# Sequencer-V01-010-eagle7.net
KiCad netlist of a schematic drawn in EAGLE
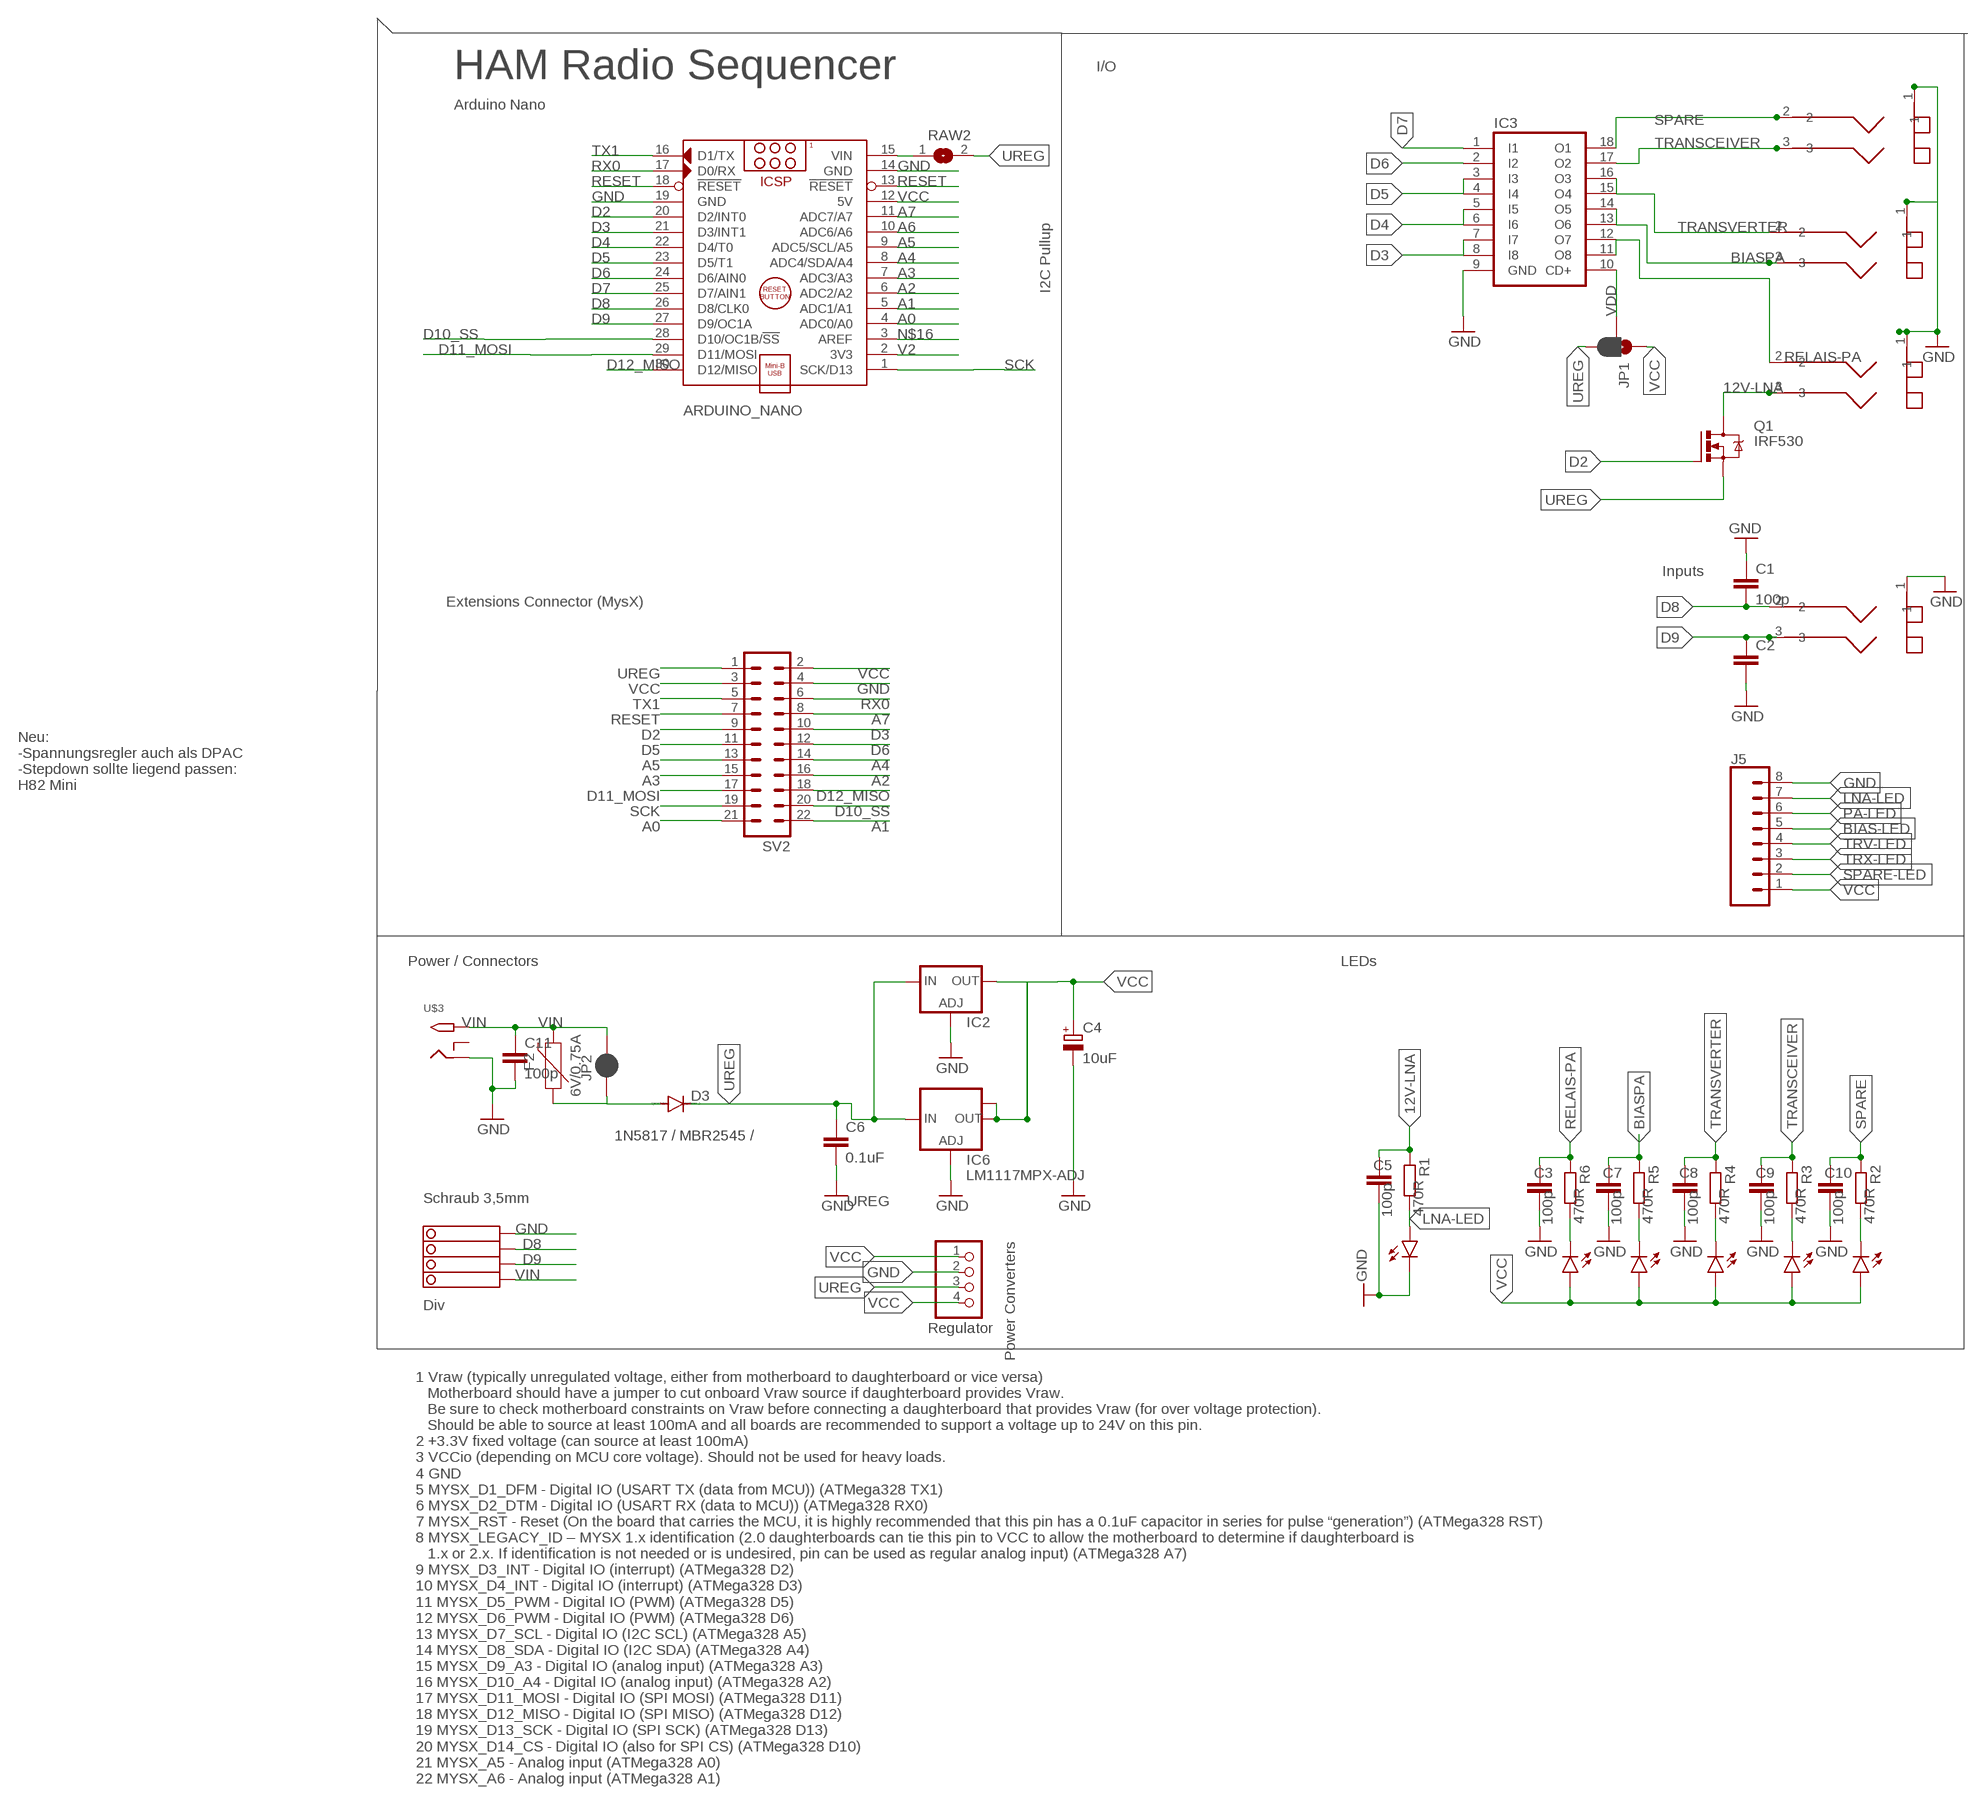
[diagram p0: schematic, sheet 1]

(export (version "E")
  (design (tool "Eeschema 10.0.6"))
  (components
    (comp (ref "ARDUINO_NANO")
      (value "ARDUINO_NANO_OHNE-BOHR")
      (footprint "eagle-import:ARDUINO_NANO")
      (libsource (lib "eagle-import") (part "ARDUINO_NANO_OHNE-BOHR"))
    )
    (comp (ref "C1")
      (value "100p")
      (footprint "eagle-import:C025-025X050")
      (libsource (lib "eagle-import") (part "C-EU025-025X050"))
    )
    (comp (ref "C2")
      (value "C-EU025-025X050")
      (footprint "eagle-import:C025-025X050")
      (libsource (lib "eagle-import") (part "C-EU025-025X050"))
    )
    (comp (ref "C3")
      (value "100p")
      (footprint "eagle-import:C025-025X050")
      (libsource (lib "eagle-import") (part "C-EU025-025X050"))
    )
    (comp (ref "C4")
      (value "10uF")
      (footprint "eagle-import:E3,5-8")
      (libsource (lib "eagle-import") (part "CPOL-EUE3.5-8"))
    )
    (comp (ref "C5")
      (value "100p")
      (footprint "eagle-import:C025-025X050")
      (libsource (lib "eagle-import") (part "C-EU025-025X050"))
    )
    (comp (ref "C6")
      (value "0.1uF")
      (footprint "eagle-import:C050-024X044")
      (libsource (lib "eagle-import") (part "C-EU050-024X044"))
    )
    (comp (ref "C7")
      (value "100p")
      (footprint "eagle-import:C025-025X050")
      (libsource (lib "eagle-import") (part "C-EU025-025X050"))
    )
    (comp (ref "C8")
      (value "100p")
      (footprint "eagle-import:C025-025X050")
      (libsource (lib "eagle-import") (part "C-EU025-025X050"))
    )
    (comp (ref "C9")
      (value "100p")
      (footprint "eagle-import:C025-025X050")
      (libsource (lib "eagle-import") (part "C-EU025-025X050"))
    )
    (comp (ref "C10")
      (value "100p")
      (footprint "eagle-import:C025-025X050")
      (libsource (lib "eagle-import") (part "C-EU025-025X050"))
    )
    (comp (ref "C11")
      (value "100p")
      (footprint "eagle-import:C025-025X050")
      (libsource (lib "eagle-import") (part "C-EU025-025X050"))
    )
    (comp (ref "D3")
      (value "1N5817 / MBR2545 /")
      (footprint "eagle-import:D-2.5")
      (libsource (lib "eagle-import") (part "DIODE-D-2.5"))
    )
    (comp (ref "F2")
      (value "6V/0.75A")
      (footprint "eagle-import:1206")
      (libsource (lib "eagle-import") (part "PPTC_THREE-QUARTER-AMP"))
    )
    (comp (ref "IC2")
      (value "LD117ADT50TR")
      (footprint "eagle-import:DPACK")
      (libsource (lib "eagle-import") (part "LD117A?DT50TR"))
    )
    (comp (ref "IC3")
      (value "ULN2803A")
      (footprint "eagle-import:DIL18")
      (libsource (lib "eagle-import") (part "ULN2803A"))
    )
    (comp (ref "IC6")
      (value "LM1117MPX-ADJ")
      (footprint "eagle-import:SOT223")
      (libsource (lib "eagle-import") (part "LM1117MPX-ADJ"))
    )
    (comp (ref "J1")
      (value "RCJ-2234")
      (footprint "eagle-import:RCJ-2221")
      (fields (field (name "MF") "CUI Devices"))
      (libsource (lib "eagle-import") (part "RCJ-2234"))
    )
    (comp (ref "J2")
      (value "RCJ-2234")
      (footprint "eagle-import:RCJ-2221")
      (fields (field (name "MF") "CUI Devices"))
      (libsource (lib "eagle-import") (part "RCJ-2234"))
    )
    (comp (ref "J3")
      (value "RCJ-2234")
      (footprint "eagle-import:RCJ-2221")
      (fields (field (name "MF") "CUI Devices"))
      (libsource (lib "eagle-import") (part "RCJ-2234"))
    )
    (comp (ref "J4")
      (value "RCJ-2234")
      (footprint "eagle-import:RCJ-2221")
      (fields (field (name "MF") "CUI Devices"))
      (libsource (lib "eagle-import") (part "RCJ-2234"))
    )
    (comp (ref "J5")
      (value "CONN_08LOCK")
      (footprint "eagle-import:1X08_LOCK")
      (libsource (lib "eagle-import") (part "CONN_08LOCK"))
    )
    (comp (ref "JP1")
      (value "JUMPER-SMT_3_1-NC_PASTE_NO-SILK")
      (footprint "eagle-import:SMT-JUMPER_3_1-NC_PASTE_NO-SILK")
      (libsource (lib "eagle-import") (part "JUMPER-SMT_3_1-NC_PASTE_NO-SILK"))
    )
    (comp (ref "JP2")
      (value "JUMPER-SMT_2_NC_PASTE_NO-SILK")
      (footprint "eagle-import:SMT-JUMPER_2_NC_PASTE_NO-SILK")
      (libsource (lib "eagle-import") (part "JUMPER-SMT_2_NC_PASTE_NO-SILK"))
    )
    (comp (ref "LED1")
      (value "LED3MM")
      (footprint "eagle-import:LED3MM")
      (libsource (lib "eagle-import") (part "LED3MM"))
    )
    (comp (ref "LED2")
      (value "LED3MM")
      (footprint "eagle-import:LED3MM")
      (libsource (lib "eagle-import") (part "LED3MM"))
    )
    (comp (ref "LED3")
      (value "LED3MM")
      (footprint "eagle-import:LED3MM")
      (libsource (lib "eagle-import") (part "LED3MM"))
    )
    (comp (ref "LED4")
      (value "LED3MM")
      (footprint "eagle-import:LED3MM")
      (libsource (lib "eagle-import") (part "LED3MM"))
    )
    (comp (ref "LED5")
      (value "LED3MM")
      (footprint "eagle-import:LED3MM")
      (libsource (lib "eagle-import") (part "LED3MM"))
    )
    (comp (ref "LED6")
      (value "LED3MM")
      (footprint "eagle-import:LED3MM")
      (libsource (lib "eagle-import") (part "LED3MM"))
    )
    (comp (ref "Q1")
      (value "IRF530")
      (footprint "eagle-import:TO220BV")
      (libsource (lib "eagle-import") (part "IRF530"))
    )
    (comp (ref "R1")
      (value "470R")
      (footprint "eagle-import:0204_5")
      (libsource (lib "eagle-import") (part "R-EU_0204/5"))
    )
    (comp (ref "R2")
      (value "470R")
      (footprint "eagle-import:0204_5")
      (libsource (lib "eagle-import") (part "R-EU_0204/5"))
    )
    (comp (ref "R3")
      (value "470R")
      (footprint "eagle-import:0204_5")
      (libsource (lib "eagle-import") (part "R-EU_0204/5"))
    )
    (comp (ref "R4")
      (value "470R")
      (footprint "eagle-import:0204_5")
      (libsource (lib "eagle-import") (part "R-EU_0204/5"))
    )
    (comp (ref "R5")
      (value "470R")
      (footprint "eagle-import:0204_5")
      (libsource (lib "eagle-import") (part "R-EU_0204/5"))
    )
    (comp (ref "R6")
      (value "470R")
      (footprint "eagle-import:0204_5")
      (libsource (lib "eagle-import") (part "R-EU_0204/5"))
    )
    (comp (ref "RAW2")
      (value "SJ")
      (footprint "eagle-import:SJ")
      (libsource (lib "eagle-import") (part "SJ"))
    )
    (comp (ref "STEPDWN")
      (value "PINHD-1X04_2.54-S")
      (footprint "eagle-import:1X04-S")
      (libsource (lib "eagle-import") (part "PINHD-1X04_2.54-S"))
    )
    (comp (ref "SV2")
      (value "MA11-2")
      (footprint "eagle-import:MA11-2")
      (libsource (lib "eagle-import") (part "MA11-2"))
    )
    (comp (ref "U$3")
      (value "2.1MMJACKTHM")
      (footprint "eagle-import:PJ-102A")
      (libsource (lib "eagle-import") (part "2.1MMJACKTHM"))
    )
    (comp (ref "X4")
      (value "1751264")
      (footprint "eagle-import:1751264")
      (libsource (lib "eagle-import") (part "1751264"))
    )
  )
  (nets
    (net (code "1") (name "/A0") (class "Default")
      (node (ref "ARDUINO_NANO") (pin "4") (pinfunction "ADC0/A0_4") (pintype "bidirectional"))
      (node (ref "SV2") (pin "21") (pinfunction "21_21") (pintype "passive"))
    )
    (net (code "2") (name "/A1") (class "Default")
      (node (ref "ARDUINO_NANO") (pin "5") (pinfunction "ADC1/A1_5") (pintype "bidirectional"))
      (node (ref "SV2") (pin "22") (pinfunction "22_22") (pintype "passive"))
    )
    (net (code "3") (name "/A2") (class "Default")
      (node (ref "ARDUINO_NANO") (pin "6") (pinfunction "ADC2/A2_6") (pintype "bidirectional"))
      (node (ref "SV2") (pin "16") (pinfunction "16_16") (pintype "passive"))
    )
    (net (code "4") (name "/A3") (class "Default")
      (node (ref "ARDUINO_NANO") (pin "7") (pinfunction "ADC3/A3_7") (pintype "bidirectional"))
      (node (ref "SV2") (pin "15") (pinfunction "15_15") (pintype "passive"))
    )
    (net (code "5") (name "/A4") (class "Default")
      (node (ref "ARDUINO_NANO") (pin "8") (pinfunction "ADC4/SDA/A4_8") (pintype "bidirectional"))
      (node (ref "SV2") (pin "14") (pinfunction "14_14") (pintype "passive"))
    )
    (net (code "6") (name "/A5") (class "Default")
      (node (ref "ARDUINO_NANO") (pin "9") (pinfunction "ADC5/SCL/A5_9") (pintype "bidirectional"))
      (node (ref "SV2") (pin "13") (pinfunction "13_13") (pintype "passive"))
    )
    (net (code "7") (name "/A6") (class "Default")
      (node (ref "ARDUINO_NANO") (pin "10") (pinfunction "ADC6/A6_10") (pintype "bidirectional"))
    )
    (net (code "8") (name "/A7") (class "Default")
      (node (ref "ARDUINO_NANO") (pin "11") (pinfunction "ADC7/A7_11") (pintype "bidirectional"))
      (node (ref "SV2") (pin "8") (pinfunction "8_8") (pintype "passive"))
    )
    (net (code "9") (name "/D10_SS") (class "Default")
      (node (ref "ARDUINO_NANO") (pin "28") (pinfunction "D10/OC1B/~{SS}_28") (pintype "bidirectional"))
      (node (ref "SV2") (pin "20") (pinfunction "20_20") (pintype "passive"))
    )
    (net (code "10") (name "/D11_MOSI") (class "Default")
      (node (ref "ARDUINO_NANO") (pin "29") (pinfunction "D11/MOSI_29") (pintype "bidirectional"))
      (node (ref "SV2") (pin "17") (pinfunction "17_17") (pintype "passive"))
    )
    (net (code "11") (name "/D12_MISO") (class "Default")
      (node (ref "ARDUINO_NANO") (pin "30") (pinfunction "D12/MISO_30") (pintype "bidirectional"))
      (node (ref "SV2") (pin "18") (pinfunction "18_18") (pintype "passive"))
    )
    (net (code "12") (name "/N$16") (class "Default")
      (node (ref "ARDUINO_NANO") (pin "3") (pinfunction "AREF_3") (pintype "input"))
    )
    (net (code "13") (name "/RESET") (class "Default")
      (node (ref "ARDUINO_NANO") (pin "13") (pinfunction "~{RESET}_13") (pintype "input"))
      (node (ref "ARDUINO_NANO") (pin "18") (pinfunction "~{RESET}_18") (pintype "input"))
      (node (ref "SV2") (pin "7") (pinfunction "7_7") (pintype "passive"))
    )
    (net (code "14") (name "/RX0") (class "Default")
      (node (ref "ARDUINO_NANO") (pin "17") (pinfunction "D0/RX_17") (pintype "bidirectional"))
      (node (ref "SV2") (pin "6") (pinfunction "6_6") (pintype "passive"))
    )
    (net (code "15") (name "/SCK") (class "Default")
      (node (ref "ARDUINO_NANO") (pin "1") (pinfunction "SCK/D13_1") (pintype "bidirectional"))
      (node (ref "SV2") (pin "19") (pinfunction "19_19") (pintype "passive"))
    )
    (net (code "16") (name "/TX1") (class "Default")
      (node (ref "ARDUINO_NANO") (pin "16") (pinfunction "D1/TX_16") (pintype "bidirectional"))
      (node (ref "SV2") (pin "5") (pinfunction "5_5") (pintype "passive"))
    )
    (net (code "17") (name "/V2") (class "Default")
      (node (ref "ARDUINO_NANO") (pin "2") (pinfunction "3V3_2") (pintype "output"))
    )
    (net (code "18") (name "/VDD") (class "Default")
      (node (ref "IC3") (pin "10") (pinfunction "CD+_10") (pintype "passive"))
      (node (ref "JP1") (pin "2") (pinfunction "2_2") (pintype "passive"))
    )
    (net (code "19") (name "/VIN") (class "Default")
      (node (ref "C11") (pin "1") (pinfunction "1_1") (pintype "passive"))
      (node (ref "F2") (pin "2") (pinfunction "2_2") (pintype "bidirectional"))
      (node (ref "JP2") (pin "2") (pinfunction "2_2") (pintype "passive"))
      (node (ref "U$3") (pin "TIP") (pinfunction "TIP_TIP") (pintype "bidirectional"))
      (node (ref "X4") (pin "1") (pinfunction "K_1") (pintype "passive"))
    )
    (net (code "20") (name "12V-LNA") (class "Default")
      (node (ref "C5") (pin "1") (pinfunction "1_1") (pintype "passive"))
      (node (ref "J3") (pin "3") (pinfunction "3_3") (pintype "bidirectional"))
      (node (ref "Q1") (pin "D") (pinfunction "D_D") (pintype "passive"))
      (node (ref "R1") (pin "1") (pinfunction "1_1") (pintype "passive"))
    )
    (net (code "21") (name "BIAS-LED") (class "Default")
      (node (ref "J5") (pin "5") (pinfunction "5_5") (pintype "passive"))
      (node (ref "LED5") (pin "K") (pinfunction "C_K") (pintype "passive"))
      (node (ref "R5") (pin "2") (pinfunction "2_2") (pintype "passive"))
    )
    (net (code "22") (name "BIASPA") (class "Default")
      (node (ref "C7") (pin "1") (pinfunction "1_1") (pintype "passive"))
      (node (ref "IC3") (pin "13") (pinfunction "O6_13") (pintype "open_collector"))
      (node (ref "IC3") (pin "14") (pinfunction "O5_14") (pintype "open_collector"))
      (node (ref "J2") (pin "3") (pinfunction "3_3") (pintype "bidirectional"))
      (node (ref "R5") (pin "1") (pinfunction "1_1") (pintype "passive"))
    )
    (net (code "23") (name "D2") (class "Default")
      (node (ref "ARDUINO_NANO") (pin "20") (pinfunction "D2/INT0_20") (pintype "bidirectional"))
      (node (ref "Q1") (pin "G") (pinfunction "G_G") (pintype "passive"))
      (node (ref "SV2") (pin "9") (pinfunction "9_9") (pintype "passive"))
    )
    (net (code "24") (name "D3") (class "Default")
      (node (ref "ARDUINO_NANO") (pin "21") (pinfunction "D3/INT1_21") (pintype "bidirectional"))
      (node (ref "IC3") (pin "7") (pinfunction "I7_7") (pintype "input"))
      (node (ref "IC3") (pin "8") (pinfunction "I8_8") (pintype "input"))
      (node (ref "SV2") (pin "10") (pinfunction "10_10") (pintype "passive"))
    )
    (net (code "25") (name "D4") (class "Default")
      (node (ref "ARDUINO_NANO") (pin "22") (pinfunction "D4/T0_22") (pintype "bidirectional"))
      (node (ref "IC3") (pin "5") (pinfunction "I5_5") (pintype "input"))
      (node (ref "IC3") (pin "6") (pinfunction "I6_6") (pintype "input"))
    )
    (net (code "26") (name "D5") (class "Default")
      (node (ref "ARDUINO_NANO") (pin "23") (pinfunction "D5/T1_23") (pintype "bidirectional"))
      (node (ref "IC3") (pin "3") (pinfunction "I3_3") (pintype "input"))
      (node (ref "IC3") (pin "4") (pinfunction "I4_4") (pintype "input"))
      (node (ref "SV2") (pin "11") (pinfunction "11_11") (pintype "passive"))
    )
    (net (code "27") (name "D6") (class "Default")
      (node (ref "ARDUINO_NANO") (pin "24") (pinfunction "D6/AIN0_24") (pintype "bidirectional"))
      (node (ref "IC3") (pin "2") (pinfunction "I2_2") (pintype "input"))
      (node (ref "SV2") (pin "12") (pinfunction "12_12") (pintype "passive"))
    )
    (net (code "28") (name "D7") (class "Default")
      (node (ref "ARDUINO_NANO") (pin "25") (pinfunction "D7/AIN1_25") (pintype "bidirectional"))
      (node (ref "IC3") (pin "1") (pinfunction "I1_1") (pintype "input"))
    )
    (net (code "29") (name "D8") (class "Default")
      (node (ref "ARDUINO_NANO") (pin "26") (pinfunction "D8/CLK0_26") (pintype "bidirectional"))
      (node (ref "C1") (pin "2") (pinfunction "2_2") (pintype "passive"))
      (node (ref "J4") (pin "2") (pinfunction "2_2") (pintype "bidirectional"))
      (node (ref "X4") (pin "3") (pinfunction "K_3") (pintype "passive"))
    )
    (net (code "30") (name "D9") (class "Default")
      (node (ref "ARDUINO_NANO") (pin "27") (pinfunction "D9/OC1A_27") (pintype "bidirectional"))
      (node (ref "C2") (pin "1") (pinfunction "1_1") (pintype "passive"))
      (node (ref "J4") (pin "3") (pinfunction "3_3") (pintype "bidirectional"))
      (node (ref "X4") (pin "2") (pinfunction "K_2") (pintype "passive"))
    )
    (net (code "31") (name "GND") (class "Default")
      (node (ref "ARDUINO_NANO") (pin "14") (pinfunction "GND_14") (pintype "power_in"))
      (node (ref "ARDUINO_NANO") (pin "19") (pinfunction "GND_19") (pintype "power_in"))
      (node (ref "C1") (pin "1") (pinfunction "1_1") (pintype "passive"))
      (node (ref "C10") (pin "2") (pinfunction "2_2") (pintype "passive"))
      (node (ref "C11") (pin "2") (pinfunction "2_2") (pintype "passive"))
      (node (ref "C2") (pin "2") (pinfunction "2_2") (pintype "passive"))
      (node (ref "C3") (pin "2") (pinfunction "2_2") (pintype "passive"))
      (node (ref "C4") (pin "-") (pinfunction "-_-") (pintype "passive"))
      (node (ref "C5") (pin "2") (pinfunction "2_2") (pintype "passive"))
      (node (ref "C6") (pin "2") (pinfunction "2_2") (pintype "passive"))
      (node (ref "C7") (pin "2") (pinfunction "2_2") (pintype "passive"))
      (node (ref "C8") (pin "2") (pinfunction "2_2") (pintype "passive"))
      (node (ref "C9") (pin "2") (pinfunction "2_2") (pintype "passive"))
      (node (ref "IC2") (pin "1") (pinfunction "ADJ_1") (pintype "input"))
      (node (ref "IC3") (pin "9") (pinfunction "GND_9") (pintype "power_in"))
      (node (ref "IC6") (pin "1") (pinfunction "ADJ_1") (pintype "input"))
      (node (ref "J1") (pin "1") (pinfunction "1_1") (pintype "bidirectional"))
      (node (ref "J2") (pin "1") (pinfunction "1_1") (pintype "bidirectional"))
      (node (ref "J3") (pin "1") (pinfunction "1_1") (pintype "bidirectional"))
      (node (ref "J4") (pin "1") (pinfunction "1_1") (pintype "bidirectional"))
      (node (ref "J5") (pin "8") (pinfunction "8_8") (pintype "passive"))
      (node (ref "LED1") (pin "K") (pinfunction "C_K") (pintype "passive"))
      (node (ref "STEPDWN") (pin "2") (pinfunction "2_2") (pintype "passive"))
      (node (ref "SV2") (pin "4") (pinfunction "4_4") (pintype "passive"))
      (node (ref "U$3") (pin "RING") (pinfunction "RING_RING") (pintype "bidirectional"))
      (node (ref "X4") (pin "4") (pinfunction "K_4") (pintype "passive"))
    )
    (net (code "32") (name "LNA-LED") (class "Default")
      (node (ref "J5") (pin "7") (pinfunction "7_7") (pintype "passive"))
      (node (ref "LED1") (pin "A") (pinfunction "A_A") (pintype "passive"))
      (node (ref "R1") (pin "2") (pinfunction "2_2") (pintype "passive"))
    )
    (net (code "33") (name "Net-(ARDUINO_NANO-VIN)") (class "Default")
      (node (ref "ARDUINO_NANO") (pin "15") (pinfunction "VIN_15") (pintype "power_in"))
      (node (ref "RAW2") (pin "1") (pinfunction "1_1") (pintype "passive"))
    )
    (net (code "34") (name "Net-(D3-PadA)") (class "Default")
      (node (ref "D3") (pin "A") (pinfunction "A_A") (pintype "passive"))
      (node (ref "F2") (pin "1") (pinfunction "1_1") (pintype "bidirectional"))
      (node (ref "JP2") (pin "1") (pinfunction "1_1") (pintype "passive"))
    )
    (net (code "35") (name "PA-LED") (class "Default")
      (node (ref "J5") (pin "6") (pinfunction "6_6") (pintype "passive"))
      (node (ref "LED6") (pin "K") (pinfunction "C_K") (pintype "passive"))
      (node (ref "R6") (pin "2") (pinfunction "2_2") (pintype "passive"))
    )
    (net (code "36") (name "RELAIS-PA") (class "Default")
      (node (ref "C3") (pin "1") (pinfunction "1_1") (pintype "passive"))
      (node (ref "IC3") (pin "11") (pinfunction "O8_11") (pintype "open_collector"))
      (node (ref "IC3") (pin "12") (pinfunction "O7_12") (pintype "open_collector"))
      (node (ref "J3") (pin "2") (pinfunction "2_2") (pintype "bidirectional"))
      (node (ref "R6") (pin "1") (pinfunction "1_1") (pintype "passive"))
    )
    (net (code "37") (name "SPARE") (class "Default")
      (node (ref "C10") (pin "1") (pinfunction "1_1") (pintype "passive"))
      (node (ref "IC3") (pin "18") (pinfunction "O1_18") (pintype "open_collector"))
      (node (ref "J1") (pin "2") (pinfunction "2_2") (pintype "bidirectional"))
      (node (ref "R2") (pin "1") (pinfunction "1_1") (pintype "passive"))
    )
    (net (code "38") (name "SPARE-LED") (class "Default")
      (node (ref "J5") (pin "2") (pinfunction "2_2") (pintype "passive"))
      (node (ref "LED2") (pin "K") (pinfunction "C_K") (pintype "passive"))
      (node (ref "R2") (pin "2") (pinfunction "2_2") (pintype "passive"))
    )
    (net (code "39") (name "TRANSCEIVER") (class "Default")
      (node (ref "C9") (pin "1") (pinfunction "1_1") (pintype "passive"))
      (node (ref "IC3") (pin "17") (pinfunction "O2_17") (pintype "open_collector"))
      (node (ref "J1") (pin "3") (pinfunction "3_3") (pintype "bidirectional"))
      (node (ref "R3") (pin "1") (pinfunction "1_1") (pintype "passive"))
    )
    (net (code "40") (name "TRANSVERTER") (class "Default")
      (node (ref "C8") (pin "1") (pinfunction "1_1") (pintype "passive"))
      (node (ref "IC3") (pin "15") (pinfunction "O4_15") (pintype "open_collector"))
      (node (ref "IC3") (pin "16") (pinfunction "O3_16") (pintype "open_collector"))
      (node (ref "J2") (pin "2") (pinfunction "2_2") (pintype "bidirectional"))
      (node (ref "R4") (pin "1") (pinfunction "1_1") (pintype "passive"))
    )
    (net (code "41") (name "TRV-LED") (class "Default")
      (node (ref "J5") (pin "4") (pinfunction "4_4") (pintype "passive"))
      (node (ref "LED4") (pin "K") (pinfunction "C_K") (pintype "passive"))
      (node (ref "R4") (pin "2") (pinfunction "2_2") (pintype "passive"))
    )
    (net (code "42") (name "TRX-LED") (class "Default")
      (node (ref "J5") (pin "3") (pinfunction "3_3") (pintype "passive"))
      (node (ref "LED3") (pin "K") (pinfunction "C_K") (pintype "passive"))
      (node (ref "R3") (pin "2") (pinfunction "2_2") (pintype "passive"))
    )
    (net (code "43") (name "UREG") (class "Default")
      (node (ref "C6") (pin "1") (pinfunction "1_1") (pintype "passive"))
      (node (ref "D3") (pin "C") (pinfunction "C_C") (pintype "passive"))
      (node (ref "IC2") (pin "3") (pinfunction "IN_3") (pintype "input"))
      (node (ref "IC6") (pin "3") (pinfunction "IN_3") (pintype "input"))
      (node (ref "JP1") (pin "3") (pinfunction "3_3") (pintype "passive"))
      (node (ref "Q1") (pin "S") (pinfunction "S_S") (pintype "passive"))
      (node (ref "RAW2") (pin "2") (pinfunction "2_2") (pintype "passive"))
      (node (ref "STEPDWN") (pin "3") (pinfunction "3_3") (pintype "passive"))
      (node (ref "SV2") (pin "1") (pinfunction "1_1") (pintype "passive"))
    )
    (net (code "44") (name "VCC") (class "Default")
      (node (ref "ARDUINO_NANO") (pin "12") (pinfunction "5V_12") (pintype "power_in"))
      (node (ref "C4") (pin "+") (pinfunction "+_+") (pintype "passive"))
      (node (ref "IC2") (pin "4") (pinfunction "OUT_4") (pintype "passive"))
      (node (ref "IC6") (pin "2") (pinfunction "OUT_2") (pintype "passive"))
      (node (ref "IC6") (pin "TAB") (pinfunction "OUT1_TAB") (pintype "passive"))
      (node (ref "J5") (pin "1") (pinfunction "1_1") (pintype "passive"))
      (node (ref "JP1") (pin "1") (pinfunction "1_1") (pintype "passive"))
      (node (ref "LED2") (pin "A") (pinfunction "A_A") (pintype "passive"))
      (node (ref "LED3") (pin "A") (pinfunction "A_A") (pintype "passive"))
      (node (ref "LED4") (pin "A") (pinfunction "A_A") (pintype "passive"))
      (node (ref "LED5") (pin "A") (pinfunction "A_A") (pintype "passive"))
      (node (ref "LED6") (pin "A") (pinfunction "A_A") (pintype "passive"))
      (node (ref "STEPDWN") (pin "1") (pinfunction "1_1") (pintype "passive"))
      (node (ref "STEPDWN") (pin "4") (pinfunction "4_4") (pintype "passive"))
      (node (ref "SV2") (pin "2") (pinfunction "2_2") (pintype "passive"))
      (node (ref "SV2") (pin "3") (pinfunction "3_3") (pintype "passive"))
    )
    (net (code "45") (name "unconnected-(U$3-PadRING_SW)") (class "Default")
      (node (ref "U$3") (pin "RING_SW") (pinfunction "RING_SW_RING_SW") (pintype "bidirectional"))
    )
  )
)
